# vme_can_can.net
KiCad netlist of a schematic drawn in Altium Designer
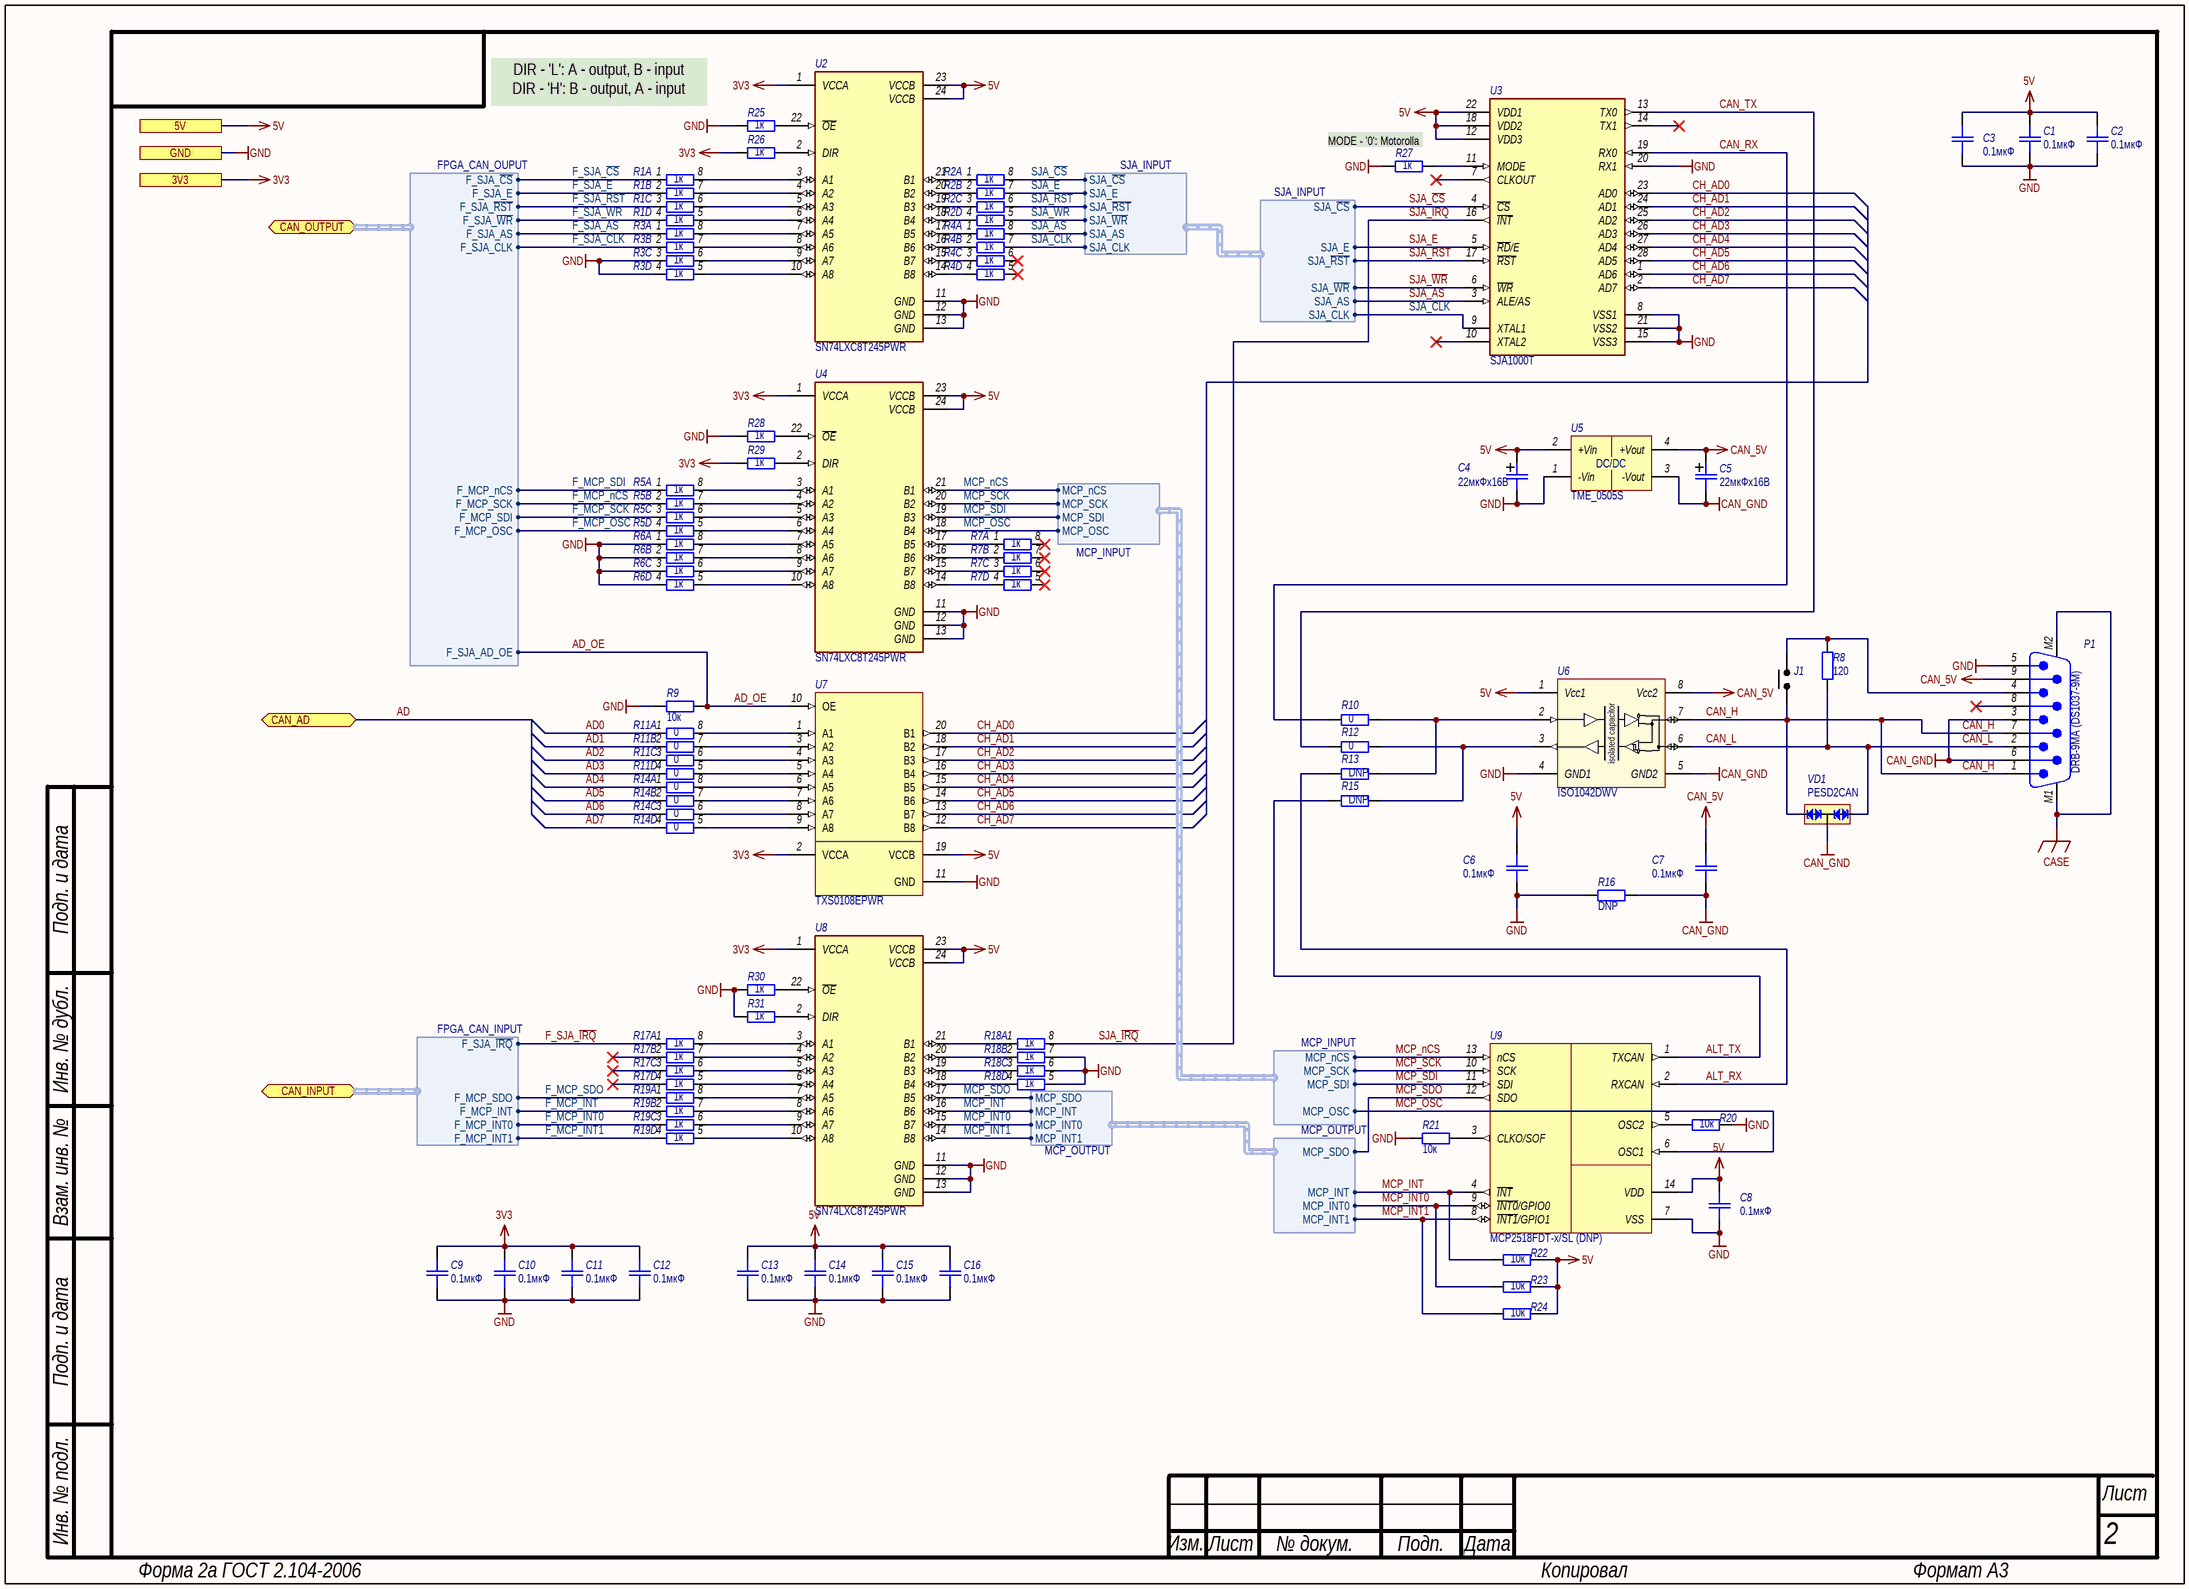
[diagram p0: vme_can_can.SchDoc]

(export (version "E")
  (design (tool "Eeschema 10.0.6"))
  (components
    (comp (ref "C1")
      (value "0.1мкФ")
      (footprint "SMD_C0805")
      (description "Capacitor")
      (libsource (lib "Passive") (part "Capacitor"))
    )
    (comp (ref "C2")
      (value "0.1мкФ")
      (footprint "SMD_C0805")
      (description "Capacitor")
      (libsource (lib "Passive") (part "Capacitor"))
    )
    (comp (ref "C3")
      (value "0.1мкФ")
      (footprint "SMD_C0805")
      (description "Capacitor")
      (libsource (lib "Passive") (part "Capacitor"))
    )
    (comp (ref "C4")
      (value "22мкФх16В")
      (footprint "SMD_size_B")
      (description "Polarized capacitor")
      (fields (field (name "Comment") "OS K53-68"))
      (libsource (lib "Passive") (part "Capacitor_pol"))
    )
    (comp (ref "C5")
      (value "22мкФх16В")
      (footprint "SMD_size_B")
      (description "Polarized capacitor")
      (fields (field (name "Comment") "OS K53-68"))
      (libsource (lib "Passive") (part "Capacitor_pol"))
    )
    (comp (ref "C6")
      (value "0.1мкФ")
      (footprint "SMD_C0805")
      (description "Capacitor")
      (libsource (lib "Passive") (part "Capacitor"))
    )
    (comp (ref "C7")
      (value "0.1мкФ")
      (footprint "SMD_C0805")
      (description "Capacitor")
      (libsource (lib "Passive") (part "Capacitor"))
    )
    (comp (ref "C8")
      (value "0.1мкФ")
      (footprint "SMD_C0805")
      (description "Capacitor")
      (libsource (lib "Passive") (part "Capacitor"))
    )
    (comp (ref "C9")
      (value "0.1мкФ")
      (footprint "SMD_C0805")
      (description "Capacitor")
      (libsource (lib "Passive") (part "Capacitor"))
    )
    (comp (ref "C10")
      (value "0.1мкФ")
      (footprint "SMD_C0805")
      (description "Capacitor")
      (libsource (lib "Passive") (part "Capacitor"))
    )
    (comp (ref "C11")
      (value "0.1мкФ")
      (footprint "SMD_C0805")
      (description "Capacitor")
      (libsource (lib "Passive") (part "Capacitor"))
    )
    (comp (ref "C12")
      (value "0.1мкФ")
      (footprint "SMD_C0805")
      (description "Capacitor")
      (libsource (lib "Passive") (part "Capacitor"))
    )
    (comp (ref "C13")
      (value "0.1мкФ")
      (footprint "SMD_C0805")
      (description "Capacitor")
      (libsource (lib "Passive") (part "Capacitor"))
    )
    (comp (ref "C14")
      (value "0.1мкФ")
      (footprint "SMD_C0805")
      (description "Capacitor")
      (libsource (lib "Passive") (part "Capacitor"))
    )
    (comp (ref "C15")
      (value "0.1мкФ")
      (footprint "SMD_C0805")
      (description "Capacitor")
      (libsource (lib "Passive") (part "Capacitor"))
    )
    (comp (ref "C16")
      (value "0.1мкФ")
      (footprint "SMD_C0805")
      (description "Capacitor")
      (libsource (lib "Passive") (part "Capacitor"))
    )
    (comp (ref "J1")
      (value "Jumper 2")
      (footprint "PLS-2")
      (description "Jumper, 2-Pin, Dual row")
      (libsource (lib "Connector") (part "Jumper 2"))
    )
    (comp (ref "P1")
      (value "DRB-9MA")
      (footprint "DRB-9MA")
      (description "D-SUB 9 pins, Male PCB Connector with Hex Screw WR-DSUB, 8.08 mm, Angled")
      (fields
        (field (name "MANUFACTURER") "Wurth Elektronik")
        (field (name "PART NUMBER") "618009231221")
        (field (name "НАИМЕНОВАНИЕ") "DRB-9MA (DS1037-9M)")
        (field (name "PUBLISHER") "WurthElektronik")
      )
      (libsource (lib "Connector") (part "DRB-9MA"))
    )
    (comp (ref "R1")
      (value "1к")
      (footprint "TC124")
      (description "4 Chip Resistor Array")
      (libsource (lib "Passive") (part "Resistor-4"))
    )
    (comp (ref "R2")
      (value "1к")
      (footprint "TC124")
      (description "4 Chip Resistor Array")
      (libsource (lib "Passive") (part "Resistor-4"))
    )
    (comp (ref "R3")
      (value "1к")
      (footprint "TC124")
      (description "4 Chip Resistor Array")
      (libsource (lib "Passive") (part "Resistor-4"))
    )
    (comp (ref "R4")
      (value "1к")
      (footprint "TC124")
      (description "4 Chip Resistor Array")
      (libsource (lib "Passive") (part "Resistor-4"))
    )
    (comp (ref "R5")
      (value "1к")
      (footprint "TC124")
      (description "4 Chip Resistor Array")
      (libsource (lib "Passive") (part "Resistor-4"))
    )
    (comp (ref "R6")
      (value "1к")
      (footprint "TC124")
      (description "4 Chip Resistor Array")
      (libsource (lib "Passive") (part "Resistor-4"))
    )
    (comp (ref "R7")
      (value "1к")
      (footprint "TC124")
      (description "4 Chip Resistor Array")
      (libsource (lib "Passive") (part "Resistor-4"))
    )
    (comp (ref "R8")
      (value "120")
      (footprint "SMD_0805")
      (description "Resistor")
      (libsource (lib "") (part "Resistor_2"))
    )
    (comp (ref "R9")
      (value "10к")
      (footprint "SMD_0805")
      (description "Resistor")
      (libsource (lib "Passive") (part "Resistor"))
    )
    (comp (ref "R10")
      (value "0")
      (footprint "SMD_0805")
      (description "Resistor")
      (libsource (lib "Passive") (part "Resistor"))
    )
    (comp (ref "R11")
      (value "0")
      (footprint "TC124")
      (description "4 Chip Resistor Array")
      (libsource (lib "Passive") (part "Resistor-4"))
    )
    (comp (ref "R12")
      (value "0")
      (footprint "SMD_0805")
      (description "Resistor")
      (libsource (lib "Passive") (part "Resistor"))
    )
    (comp (ref "R13")
      (value "DNP")
      (footprint "SMD_0805")
      (description "Resistor")
      (libsource (lib "Passive") (part "Resistor"))
    )
    (comp (ref "R14")
      (value "0")
      (footprint "TC124")
      (description "4 Chip Resistor Array")
      (libsource (lib "Passive") (part "Resistor-4"))
    )
    (comp (ref "R15")
      (value "DNP")
      (footprint "SMD_0805")
      (description "Resistor")
      (libsource (lib "Passive") (part "Resistor"))
    )
    (comp (ref "R16")
      (value "DNP")
      (footprint "SMD_0805")
      (description "Resistor")
      (libsource (lib "Passive") (part "Resistor"))
    )
    (comp (ref "R17")
      (value "1к")
      (footprint "TC124")
      (description "4 Chip Resistor Array")
      (libsource (lib "Passive") (part "Resistor-4"))
    )
    (comp (ref "R18")
      (value "1к")
      (footprint "TC124")
      (description "4 Chip Resistor Array")
      (libsource (lib "Passive") (part "Resistor-4"))
    )
    (comp (ref "R19")
      (value "1к")
      (footprint "TC124")
      (description "4 Chip Resistor Array")
      (libsource (lib "Passive") (part "Resistor-4"))
    )
    (comp (ref "R20")
      (value "10к")
      (footprint "SMD_0805")
      (description "Resistor")
      (libsource (lib "Passive") (part "Resistor"))
    )
    (comp (ref "R21")
      (value "10к")
      (footprint "SMD_0805")
      (description "Resistor")
      (libsource (lib "") (part "Resistor_1"))
    )
    (comp (ref "R22")
      (value "10к")
      (footprint "SMD_0805")
      (description "Resistor")
      (libsource (lib "Passive") (part "Resistor"))
    )
    (comp (ref "R23")
      (value "10к")
      (footprint "SMD_0805")
      (description "Resistor")
      (libsource (lib "Passive") (part "Resistor"))
    )
    (comp (ref "R24")
      (value "10к")
      (footprint "SMD_0805")
      (description "Resistor")
      (libsource (lib "Passive") (part "Resistor"))
    )
    (comp (ref "R25")
      (value "1к")
      (footprint "SMD_0805")
      (description "Resistor")
      (libsource (lib "Passive") (part "Resistor"))
    )
    (comp (ref "R26")
      (value "1к")
      (footprint "SMD_0805")
      (description "Resistor")
      (libsource (lib "Passive") (part "Resistor"))
    )
    (comp (ref "R27")
      (value "1к")
      (footprint "SMD_0805")
      (description "Resistor")
      (libsource (lib "Passive") (part "Resistor"))
    )
    (comp (ref "R28")
      (value "1к")
      (footprint "SMD_0805")
      (description "Resistor")
      (libsource (lib "Passive") (part "Resistor"))
    )
    (comp (ref "R29")
      (value "1к")
      (footprint "SMD_0805")
      (description "Resistor")
      (libsource (lib "Passive") (part "Resistor"))
    )
    (comp (ref "R30")
      (value "1к")
      (footprint "SMD_0805")
      (description "Resistor")
      (libsource (lib "Passive") (part "Resistor"))
    )
    (comp (ref "R31")
      (value "1к")
      (footprint "SMD_0805")
      (description "Resistor")
      (libsource (lib "Passive") (part "Resistor"))
    )
    (comp (ref "U2")
      (value "SN74LXC8T245PWR")
      (footprint "TSSOP-24")
      (description "Dual-Supply Bus Transceiver with Configurable Level Shifting\r\nand 3-State Outputs")
      (fields (field (name "НАИМЕНОВАНИЕ") "SN74LXC8T245PWR"))
      (libsource (lib "Transceiver") (part "SN74LXC8T245PWR"))
    )
    (comp (ref "U3")
      (value "SJA1000T")
      (footprint "SO28")
      (description "IC STAND-ALONE CAN CTRLR 28-SOIC")
      (fields
        (field (name "MANUFACTURER PART NUMBER") "SJA1000T/N1,118")
        (field (name "OCTOPART") "https://octopart.com/sja1000t%2Fn1%2C118-nxp+semiconductors-9518151")
        (field (name "НАИМЕНОВАНИЕ") "SJA1000T")
      )
      (libsource (lib "Interface_Controller") (part "SJA1000"))
    )
    (comp (ref "U4")
      (value "SN74LXC8T245PWR")
      (footprint "TSSOP-24")
      (description "Dual-Supply Bus Transceiver with Configurable Level Shifting\r\nand 3-State Outputs")
      (fields (field (name "НАИМЕНОВАНИЕ") "SN74LXC8T245PWR"))
      (libsource (lib "Transceiver") (part "SN74LXC8T245PWR"))
    )
    (comp (ref "U5")
      (value "TME_0505S")
      (footprint "PCBComponent_1")
      (description "DC-DC, 1W, Fixed input voltage, isolated & unregulated single output")
      (fields (field (name "НАИМЕНОВАНИЕ") "TME_0505S"))
      (libsource (lib "DC_DC") (part "TME_xxxxS"))
    )
    (comp (ref "U6")
      (value "ISO1042")
      (footprint "SOIC-8-WIDE")
      (description "Isolated CAN Transceiver")
      (fields (field (name "НАИМЕНОВАНИЕ") "ISO1042DWV"))
      (libsource (lib "Transceiver") (part "ISO1042"))
    )
    (comp (ref "U7")
      (value "TXS0108EPWR")
      (footprint "TSSOP-20")
      (fields (field (name "НАИМЕНОВАНИЕ") "TXS0108EPWR"))
      (libsource (lib "Transceiver") (part "TXS0108EPWR"))
    )
    (comp (ref "U8")
      (value "SN74LXC8T245PWR")
      (footprint "TSSOP-24")
      (description "Dual-Supply Bus Transceiver with Configurable Level Shifting\r\nand 3-State Outputs")
      (fields (field (name "НАИМЕНОВАНИЕ") "SN74LXC8T245PWR"))
      (libsource (lib "Transceiver") (part "SN74LXC8T245PWR"))
    )
    (comp (ref "U9")
      (value "MCP2518FDT-x/SL")
      (footprint "SOIC-14")
      (description "CAN FD Controller with SPI Interface")
      (fields (field (name "НАИМЕНОВАНИЕ") "MCP2518FDT-x/SL (DNP)"))
      (libsource (lib "Interface_Controller") (part "MCP2518FDT-x_SL"))
    )
    (comp (ref "VD1")
      (value "PESD2CAN")
      (footprint "SOT-23")
      (description "CAN bus ESD protection diode")
      (fields (field (name "НАИМЕНОВАНИЕ") "PESD2CAN"))
      (libsource (lib "Diod") (part "PESD2CAN"))
    )
  )
  (nets
    (net (code "7") (name "/AD0") (class "Default")
      (node (ref "R11") (pin "1") (pinfunction "1_1") (pintype "passive"))
    )
    (net (code "8") (name "/AD1") (class "Default")
      (node (ref "R11") (pin "2") (pinfunction "2_2") (pintype "passive"))
    )
    (net (code "9") (name "/AD2") (class "Default")
      (node (ref "R11") (pin "3") (pinfunction "3_3") (pintype "passive"))
    )
    (net (code "10") (name "/AD3") (class "Default")
      (node (ref "R11") (pin "4") (pinfunction "4_4") (pintype "passive"))
    )
    (net (code "11") (name "/AD4") (class "Default")
      (node (ref "R14") (pin "1") (pinfunction "1_1") (pintype "passive"))
    )
    (net (code "12") (name "/AD5") (class "Default")
      (node (ref "R14") (pin "2") (pinfunction "2_2") (pintype "passive"))
    )
    (net (code "13") (name "/AD6") (class "Default")
      (node (ref "R14") (pin "3") (pinfunction "3_3") (pintype "passive"))
    )
    (net (code "14") (name "/AD7") (class "Default")
      (node (ref "R14") (pin "4") (pinfunction "4_4") (pintype "passive"))
    )
    (net (code "15") (name "/AD_OE") (class "Default")
      (node (ref "R9") (pin "1") (pinfunction "1_1") (pintype "passive"))
      (node (ref "U7") (pin "10") (pinfunction "OE_10") (pintype "input"))
    )
    (net (code "16") (name "/ALT_RX") (class "Default")
      (node (ref "R13") (pin "2") (pinfunction "2_2") (pintype "passive"))
      (node (ref "U9") (pin "2") (pinfunction "RXCAN_2") (pintype "input"))
    )
    (net (code "17") (name "/ALT_TX") (class "Default")
      (node (ref "R15") (pin "2") (pinfunction "2_2") (pintype "passive"))
      (node (ref "U9") (pin "1") (pinfunction "TXCAN_1") (pintype "output"))
    )
    (net (code "18") (name "/CAN_H") (class "Default")
      (node (ref "J1") (pin "1") (pinfunction "1_1") (pintype "passive"))
      (node (ref "P1") (pin "1") (pinfunction "1_1") (pintype "passive"))
      (node (ref "P1") (pin "7") (pinfunction "7_7") (pintype "passive"))
      (node (ref "U6") (pin "7") (pinfunction "CANH_7") (pintype "bidirectional"))
      (node (ref "VD1") (pin "2") (pinfunction "C2_2") (pintype "passive"))
    )
    (net (code "19") (name "/CAN_L") (class "Default")
      (node (ref "P1") (pin "2") (pinfunction "2_2") (pintype "passive"))
      (node (ref "R8") (pin "1") (pinfunction "1_1") (pintype "passive"))
      (node (ref "U6") (pin "6") (pinfunction "CANL_6") (pintype "bidirectional"))
      (node (ref "VD1") (pin "1") (pinfunction "C1_1") (pintype "passive"))
    )
    (net (code "20") (name "/CAN_RX") (class "Default")
      (node (ref "R10") (pin "2") (pinfunction "2_2") (pintype "passive"))
      (node (ref "U3") (pin "19") (pinfunction "RX0_19") (pintype "input"))
    )
    (net (code "21") (name "/CAN_TX") (class "Default")
      (node (ref "R12") (pin "2") (pinfunction "2_2") (pintype "passive"))
      (node (ref "U3") (pin "13") (pinfunction "TX0_13") (pintype "output"))
    )
    (net (code "22") (name "/CH_AD0") (class "Default")
      (node (ref "U3") (pin "23") (pinfunction "AD0_23") (pintype "bidirectional"))
      (node (ref "U7") (pin "20") (pinfunction "B1_20") (pintype "output"))
    )
    (net (code "23") (name "/CH_AD1") (class "Default")
      (node (ref "U3") (pin "24") (pinfunction "AD1_24") (pintype "bidirectional"))
      (node (ref "U7") (pin "18") (pinfunction "B2_18") (pintype "output"))
    )
    (net (code "24") (name "/CH_AD2") (class "Default")
      (node (ref "U3") (pin "25") (pinfunction "AD2_25") (pintype "bidirectional"))
      (node (ref "U7") (pin "17") (pinfunction "B3_17") (pintype "output"))
    )
    (net (code "25") (name "/CH_AD3") (class "Default")
      (node (ref "U3") (pin "26") (pinfunction "AD3_26") (pintype "bidirectional"))
      (node (ref "U7") (pin "16") (pinfunction "B4_16") (pintype "output"))
    )
    (net (code "26") (name "/CH_AD4") (class "Default")
      (node (ref "U3") (pin "27") (pinfunction "AD4_27") (pintype "bidirectional"))
      (node (ref "U7") (pin "15") (pinfunction "B5_15") (pintype "output"))
    )
    (net (code "27") (name "/CH_AD5") (class "Default")
      (node (ref "U3") (pin "28") (pinfunction "AD5_28") (pintype "bidirectional"))
      (node (ref "U7") (pin "14") (pinfunction "B6_14") (pintype "output"))
    )
    (net (code "28") (name "/CH_AD6") (class "Default")
      (node (ref "U3") (pin "1") (pinfunction "AD6_1") (pintype "bidirectional"))
      (node (ref "U7") (pin "13") (pinfunction "B7_13") (pintype "output"))
    )
    (net (code "29") (name "/CH_AD7") (class "Default")
      (node (ref "U3") (pin "2") (pinfunction "AD7_2") (pintype "bidirectional"))
      (node (ref "U7") (pin "12") (pinfunction "B8_12") (pintype "output"))
    )
    (net (code "30") (name "/F_MCP_INT") (class "Default")
      (node (ref "R19") (pin "2") (pinfunction "2_2") (pintype "passive"))
    )
    (net (code "31") (name "/F_MCP_INT0") (class "Default")
      (node (ref "R19") (pin "3") (pinfunction "3_3") (pintype "passive"))
    )
    (net (code "32") (name "/F_MCP_INT1") (class "Default")
      (node (ref "R19") (pin "4") (pinfunction "4_4") (pintype "passive"))
    )
    (net (code "33") (name "/F_MCP_OSC") (class "Default")
      (node (ref "R5") (pin "4") (pinfunction "4_4") (pintype "passive"))
    )
    (net (code "34") (name "/F_MCP_SCK") (class "Default")
      (node (ref "R5") (pin "3") (pinfunction "3_3") (pintype "passive"))
    )
    (net (code "35") (name "/F_MCP_SDI") (class "Default")
      (node (ref "R5") (pin "1") (pinfunction "1_1") (pintype "passive"))
    )
    (net (code "36") (name "/F_MCP_SDO") (class "Default")
      (node (ref "R19") (pin "1") (pinfunction "1_1") (pintype "passive"))
    )
    (net (code "37") (name "/F_MCP_nCS") (class "Default")
      (node (ref "R5") (pin "2") (pinfunction "2_2") (pintype "passive"))
    )
    (net (code "38") (name "/F_SJA_AS") (class "Default")
      (node (ref "R3") (pin "1") (pinfunction "1_1") (pintype "passive"))
    )
    (net (code "39") (name "/F_SJA_CLK") (class "Default")
      (node (ref "R3") (pin "2") (pinfunction "2_2") (pintype "passive"))
    )
    (net (code "40") (name "/F_SJA_E") (class "Default")
      (node (ref "R1") (pin "2") (pinfunction "2_2") (pintype "passive"))
    )
    (net (code "41") (name "/F_SJA_~{CS}") (class "Default")
      (node (ref "R1") (pin "1") (pinfunction "1_1") (pintype "passive"))
    )
    (net (code "42") (name "/F_SJA_~{IRQ}") (class "Default")
      (node (ref "R17") (pin "1") (pinfunction "1_1") (pintype "passive"))
    )
    (net (code "43") (name "/F_SJA_~{RST}") (class "Default")
      (node (ref "R1") (pin "3") (pinfunction "3_3") (pintype "passive"))
    )
    (net (code "44") (name "/F_SJA_~{WR}") (class "Default")
      (node (ref "R1") (pin "4") (pinfunction "4_4") (pintype "passive"))
    )
    (net (code "45") (name "/MCP_INT") (class "Default")
      (node (ref "R22") (pin "2") (pinfunction "2_2") (pintype "passive"))
      (node (ref "U8") (pin "16") (pinfunction "B6_16") (pintype "bidirectional"))
      (node (ref "U9") (pin "4") (pinfunction "~{INT}_4") (pintype "output"))
    )
    (net (code "46") (name "/MCP_INT0") (class "Default")
      (node (ref "R23") (pin "2") (pinfunction "2_2") (pintype "passive"))
      (node (ref "U8") (pin "15") (pinfunction "B7_15") (pintype "bidirectional"))
      (node (ref "U9") (pin "9") (pinfunction "~{INT0}/GPIO0_9") (pintype "bidirectional"))
    )
    (net (code "47") (name "/MCP_INT1") (class "Default")
      (node (ref "R24") (pin "2") (pinfunction "2_2") (pintype "passive"))
      (node (ref "U8") (pin "14") (pinfunction "B8_14") (pintype "bidirectional"))
      (node (ref "U9") (pin "8") (pinfunction "~{INT1}/GPIO1_8") (pintype "bidirectional"))
    )
    (net (code "48") (name "/MCP_OSC") (class "Default")
      (node (ref "U4") (pin "18") (pinfunction "B4_18") (pintype "bidirectional"))
      (node (ref "U9") (pin "6") (pinfunction "OSC1_6") (pintype "input"))
    )
    (net (code "49") (name "/MCP_SCK") (class "Default")
      (node (ref "U4") (pin "20") (pinfunction "B2_20") (pintype "bidirectional"))
      (node (ref "U9") (pin "10") (pinfunction "SCK_10") (pintype "input"))
    )
    (net (code "50") (name "/MCP_SDI") (class "Default")
      (node (ref "U4") (pin "19") (pinfunction "B3_19") (pintype "bidirectional"))
      (node (ref "U9") (pin "11") (pinfunction "SDI_11") (pintype "input"))
    )
    (net (code "51") (name "/MCP_SDO") (class "Default")
      (node (ref "U8") (pin "17") (pinfunction "B5_17") (pintype "bidirectional"))
      (node (ref "U9") (pin "12") (pinfunction "SDO_12") (pintype "output"))
    )
    (net (code "52") (name "/MCP_nCS") (class "Default")
      (node (ref "U4") (pin "21") (pinfunction "B1_21") (pintype "bidirectional"))
      (node (ref "U9") (pin "13") (pinfunction "nCS_13") (pintype "input"))
    )
    (net (code "53") (name "/SJA_AS") (class "Default")
      (node (ref "R4") (pin "8") (pinfunction "8_8") (pintype "passive"))
      (node (ref "U3") (pin "3") (pinfunction "ALE/AS_3") (pintype "input"))
    )
    (net (code "54") (name "/SJA_CLK") (class "Default")
      (node (ref "R4") (pin "7") (pinfunction "7_7") (pintype "passive"))
      (node (ref "U3") (pin "9") (pinfunction "XTAL1_9") (pintype "passive"))
    )
    (net (code "55") (name "/SJA_E") (class "Default")
      (node (ref "R2") (pin "7") (pinfunction "7_7") (pintype "passive"))
      (node (ref "U3") (pin "5") (pinfunction "~{RD}/E_5") (pintype "input"))
    )
    (net (code "56") (name "/SJA_~{CS}") (class "Default")
      (node (ref "R2") (pin "8") (pinfunction "8_8") (pintype "passive"))
      (node (ref "U3") (pin "4") (pinfunction "~{CS}_4") (pintype "input"))
    )
    (net (code "57") (name "/SJA_~{IRQ}") (class "Default")
      (node (ref "R18") (pin "8") (pinfunction "8_8") (pintype "passive"))
      (node (ref "U3") (pin "16") (pinfunction "~{INT}_16") (pintype "output"))
    )
    (net (code "58") (name "/SJA_~{RST}") (class "Default")
      (node (ref "R2") (pin "6") (pinfunction "6_6") (pintype "passive"))
      (node (ref "U3") (pin "17") (pinfunction "~{RST}_17") (pintype "input"))
    )
    (net (code "59") (name "/SJA_~{WR}") (class "Default")
      (node (ref "R2") (pin "5") (pinfunction "5_5") (pintype "passive"))
      (node (ref "U3") (pin "6") (pinfunction "~{WR}_6") (pintype "input"))
    )
    (net (code "66") (name "3V3") (class "Default")
      (node (ref "C10") (pin "2") (pinfunction "2_2") (pintype "passive"))
      (node (ref "C11") (pin "2") (pinfunction "2_2") (pintype "passive"))
      (node (ref "C12") (pin "2") (pinfunction "2_2") (pintype "passive"))
      (node (ref "C9") (pin "2") (pinfunction "2_2") (pintype "passive"))
      (node (ref "R26") (pin "2") (pinfunction "2_2") (pintype "passive"))
      (node (ref "R29") (pin "2") (pinfunction "2_2") (pintype "passive"))
      (node (ref "U2") (pin "1") (pinfunction "VCCA_1") (pintype "power_in"))
      (node (ref "U4") (pin "1") (pinfunction "VCCA_1") (pintype "power_in"))
      (node (ref "U7") (pin "2") (pinfunction "VCCA_2") (pintype "power_in"))
      (node (ref "U8") (pin "1") (pinfunction "VCCA_1") (pintype "power_in"))
    )
    (net (code "67") (name "5V") (class "Default")
      (node (ref "C1") (pin "2") (pinfunction "2_2") (pintype "passive"))
      (node (ref "C13") (pin "2") (pinfunction "2_2") (pintype "passive"))
      (node (ref "C14") (pin "2") (pinfunction "2_2") (pintype "passive"))
      (node (ref "C15") (pin "2") (pinfunction "2_2") (pintype "passive"))
      (node (ref "C16") (pin "2") (pinfunction "2_2") (pintype "passive"))
      (node (ref "C2") (pin "2") (pinfunction "2_2") (pintype "passive"))
      (node (ref "C3") (pin "2") (pinfunction "2_2") (pintype "passive"))
      (node (ref "C4") (pin "1") (pinfunction "1_1") (pintype "passive"))
      (node (ref "C6") (pin "2") (pinfunction "2_2") (pintype "passive"))
      (node (ref "C8") (pin "2") (pinfunction "2_2") (pintype "passive"))
      (node (ref "R22") (pin "1") (pinfunction "1_1") (pintype "passive"))
      (node (ref "R23") (pin "1") (pinfunction "1_1") (pintype "passive"))
      (node (ref "R24") (pin "1") (pinfunction "1_1") (pintype "passive"))
      (node (ref "U2") (pin "23") (pinfunction "VCCB_23") (pintype "power_in"))
      (node (ref "U2") (pin "24") (pinfunction "VCCB_24") (pintype "power_in"))
      (node (ref "U3") (pin "12") (pinfunction "VDD3_12") (pintype "power_in"))
      (node (ref "U3") (pin "18") (pinfunction "VDD2_18") (pintype "power_in"))
      (node (ref "U3") (pin "22") (pinfunction "VDD1_22") (pintype "power_in"))
      (node (ref "U4") (pin "23") (pinfunction "VCCB_23") (pintype "power_in"))
      (node (ref "U4") (pin "24") (pinfunction "VCCB_24") (pintype "power_in"))
      (node (ref "U5") (pin "2") (pinfunction "+Vin_2") (pintype "power_in"))
      (node (ref "U6") (pin "1") (pinfunction "Vcc1_1") (pintype "power_in"))
      (node (ref "U7") (pin "19") (pinfunction "VCCB_19") (pintype "power_in"))
      (node (ref "U8") (pin "23") (pinfunction "VCCB_23") (pintype "power_in"))
      (node (ref "U8") (pin "24") (pinfunction "VCCB_24") (pintype "power_in"))
      (node (ref "U9") (pin "14") (pinfunction "VDD_14") (pintype "power_in"))
    )
    (net (code "68") (name "CAN_5V") (class "Default")
      (node (ref "C5") (pin "1") (pinfunction "1_1") (pintype "passive"))
      (node (ref "C7") (pin "2") (pinfunction "2_2") (pintype "passive"))
      (node (ref "P1") (pin "9") (pinfunction "9_9") (pintype "passive"))
      (node (ref "U5") (pin "4") (pinfunction "+Vout_4") (pintype "power_in"))
      (node (ref "U6") (pin "8") (pinfunction "Vcc2_8") (pintype "power_in"))
    )
    (net (code "69") (name "CAN_GND") (class "Default")
      (node (ref "C5") (pin "2") (pinfunction "2_2") (pintype "passive"))
      (node (ref "C7") (pin "1") (pinfunction "1_1") (pintype "passive"))
      (node (ref "P1") (pin "3") (pinfunction "3_3") (pintype "passive"))
      (node (ref "P1") (pin "6") (pinfunction "6_6") (pintype "passive"))
      (node (ref "R16") (pin "1") (pinfunction "1_1") (pintype "passive"))
      (node (ref "U5") (pin "3") (pinfunction "-Vout_3") (pintype "power_in"))
      (node (ref "U6") (pin "5") (pinfunction "GND2_5") (pintype "power_in"))
      (node (ref "VD1") (pin "3") (pinfunction "CC_3") (pintype "passive"))
    )
    (net (code "70") (name "CASE") (class "Default")
      (node (ref "P1") (pin "M1") (pinfunction "M1_M1") (pintype "passive"))
      (node (ref "P1") (pin "M2") (pinfunction "M2_M2") (pintype "passive"))
    )
    (net (code "71") (name "GND") (class "Default")
      (node (ref "C1") (pin "1") (pinfunction "1_1") (pintype "passive"))
      (node (ref "C10") (pin "1") (pinfunction "1_1") (pintype "passive"))
      (node (ref "C11") (pin "1") (pinfunction "1_1") (pintype "passive"))
      (node (ref "C12") (pin "1") (pinfunction "1_1") (pintype "passive"))
      (node (ref "C13") (pin "1") (pinfunction "1_1") (pintype "passive"))
      (node (ref "C14") (pin "1") (pinfunction "1_1") (pintype "passive"))
      (node (ref "C15") (pin "1") (pinfunction "1_1") (pintype "passive"))
      (node (ref "C16") (pin "1") (pinfunction "1_1") (pintype "passive"))
      (node (ref "C2") (pin "1") (pinfunction "1_1") (pintype "passive"))
      (node (ref "C3") (pin "1") (pinfunction "1_1") (pintype "passive"))
      (node (ref "C4") (pin "2") (pinfunction "2_2") (pintype "passive"))
      (node (ref "C6") (pin "1") (pinfunction "1_1") (pintype "passive"))
      (node (ref "C8") (pin "1") (pinfunction "1_1") (pintype "passive"))
      (node (ref "C9") (pin "1") (pinfunction "1_1") (pintype "passive"))
      (node (ref "P1") (pin "5") (pinfunction "5_5") (pintype "passive"))
      (node (ref "R16") (pin "2") (pinfunction "2_2") (pintype "passive"))
      (node (ref "R18") (pin "5") (pinfunction "5_5") (pintype "passive"))
      (node (ref "R18") (pin "6") (pinfunction "6_6") (pintype "passive"))
      (node (ref "R18") (pin "7") (pinfunction "7_7") (pintype "passive"))
      (node (ref "R20") (pin "1") (pinfunction "1_1") (pintype "passive"))
      (node (ref "R21") (pin "1") (pinfunction "1_1") (pintype "passive"))
      (node (ref "R25") (pin "2") (pinfunction "2_2") (pintype "passive"))
      (node (ref "R27") (pin "2") (pinfunction "2_2") (pintype "passive"))
      (node (ref "R28") (pin "2") (pinfunction "2_2") (pintype "passive"))
      (node (ref "R3") (pin "3") (pinfunction "3_3") (pintype "passive"))
      (node (ref "R3") (pin "4") (pinfunction "4_4") (pintype "passive"))
      (node (ref "R30") (pin "2") (pinfunction "2_2") (pintype "passive"))
      (node (ref "R31") (pin "2") (pinfunction "2_2") (pintype "passive"))
      (node (ref "R6") (pin "1") (pinfunction "1_1") (pintype "passive"))
      (node (ref "R6") (pin "2") (pinfunction "2_2") (pintype "passive"))
      (node (ref "R6") (pin "3") (pinfunction "3_3") (pintype "passive"))
      (node (ref "R6") (pin "4") (pinfunction "4_4") (pintype "passive"))
      (node (ref "R9") (pin "2") (pinfunction "2_2") (pintype "passive"))
      (node (ref "U2") (pin "11") (pinfunction "GND_11") (pintype "power_in"))
      (node (ref "U2") (pin "12") (pinfunction "GND_12") (pintype "power_in"))
      (node (ref "U2") (pin "13") (pinfunction "GND_13") (pintype "power_in"))
      (node (ref "U3") (pin "15") (pinfunction "VSS3_15") (pintype "power_in"))
      (node (ref "U3") (pin "20") (pinfunction "RX1_20") (pintype "input"))
      (node (ref "U3") (pin "21") (pinfunction "VSS2_21") (pintype "power_in"))
      (node (ref "U3") (pin "8") (pinfunction "VSS1_8") (pintype "power_in"))
      (node (ref "U4") (pin "11") (pinfunction "GND_11") (pintype "power_in"))
      (node (ref "U4") (pin "12") (pinfunction "GND_12") (pintype "power_in"))
      (node (ref "U4") (pin "13") (pinfunction "GND_13") (pintype "power_in"))
      (node (ref "U5") (pin "1") (pinfunction "-Vin_1") (pintype "power_in"))
      (node (ref "U6") (pin "4") (pinfunction "GND1_4") (pintype "power_in"))
      (node (ref "U7") (pin "11") (pinfunction "GND_11") (pintype "power_in"))
      (node (ref "U8") (pin "11") (pinfunction "GND_11") (pintype "power_in"))
      (node (ref "U8") (pin "12") (pinfunction "GND_12") (pintype "power_in"))
      (node (ref "U8") (pin "13") (pinfunction "GND_13") (pintype "power_in"))
      (node (ref "U9") (pin "7") (pinfunction "VSS_7") (pintype "power_in"))
    )
    (net (code "72") (name "Net-(J1-Pad2)") (class "Default")
      (node (ref "J1") (pin "2") (pinfunction "2_2") (pintype "passive"))
      (node (ref "P1") (pin "4") (pinfunction "4_4") (pintype "passive"))
      (node (ref "R8") (pin "2") (pinfunction "2_2") (pintype "passive"))
    )
    (net (code "73") (name "Net-(U2-A1)") (class "Default")
      (node (ref "R1") (pin "8") (pinfunction "8_8") (pintype "passive"))
      (node (ref "U2") (pin "3") (pinfunction "A1_3") (pintype "bidirectional"))
    )
    (net (code "74") (name "Net-(U2-A2)") (class "Default")
      (node (ref "R1") (pin "7") (pinfunction "7_7") (pintype "passive"))
      (node (ref "U2") (pin "4") (pinfunction "A2_4") (pintype "bidirectional"))
    )
    (net (code "75") (name "Net-(U2-A3)") (class "Default")
      (node (ref "R1") (pin "6") (pinfunction "6_6") (pintype "passive"))
      (node (ref "U2") (pin "5") (pinfunction "A3_5") (pintype "bidirectional"))
    )
    (net (code "76") (name "Net-(U2-A4)") (class "Default")
      (node (ref "R1") (pin "5") (pinfunction "5_5") (pintype "passive"))
      (node (ref "U2") (pin "6") (pinfunction "A4_6") (pintype "bidirectional"))
    )
    (net (code "77") (name "Net-(U2-A5)") (class "Default")
      (node (ref "R3") (pin "8") (pinfunction "8_8") (pintype "passive"))
      (node (ref "U2") (pin "7") (pinfunction "A5_7") (pintype "bidirectional"))
    )
    (net (code "78") (name "Net-(U2-A6)") (class "Default")
      (node (ref "R3") (pin "7") (pinfunction "7_7") (pintype "passive"))
      (node (ref "U2") (pin "8") (pinfunction "A6_8") (pintype "bidirectional"))
    )
    (net (code "79") (name "Net-(U2-A7)") (class "Default")
      (node (ref "R3") (pin "6") (pinfunction "6_6") (pintype "passive"))
      (node (ref "U2") (pin "9") (pinfunction "A7_9") (pintype "bidirectional"))
    )
    (net (code "80") (name "Net-(U2-A8)") (class "Default")
      (node (ref "R3") (pin "5") (pinfunction "5_5") (pintype "passive"))
      (node (ref "U2") (pin "10") (pinfunction "A8_10") (pintype "bidirectional"))
    )
    (net (code "81") (name "Net-(U2-B1)") (class "Default")
      (node (ref "R2") (pin "1") (pinfunction "1_1") (pintype "passive"))
      (node (ref "U2") (pin "21") (pinfunction "B1_21") (pintype "bidirectional"))
    )
    (net (code "82") (name "Net-(U2-B2)") (class "Default")
      (node (ref "R2") (pin "2") (pinfunction "2_2") (pintype "passive"))
      (node (ref "U2") (pin "20") (pinfunction "B2_20") (pintype "bidirectional"))
    )
    (net (code "83") (name "Net-(U2-B3)") (class "Default")
      (node (ref "R2") (pin "3") (pinfunction "3_3") (pintype "passive"))
      (node (ref "U2") (pin "19") (pinfunction "B3_19") (pintype "bidirectional"))
    )
    (net (code "84") (name "Net-(U2-B4)") (class "Default")
      (node (ref "R2") (pin "4") (pinfunction "4_4") (pintype "passive"))
      (node (ref "U2") (pin "18") (pinfunction "B4_18") (pintype "bidirectional"))
    )
    (net (code "85") (name "Net-(U2-B5)") (class "Default")
      (node (ref "R4") (pin "1") (pinfunction "1_1") (pintype "passive"))
      (node (ref "U2") (pin "17") (pinfunction "B5_17") (pintype "bidirectional"))
    )
    (net (code "86") (name "Net-(U2-B6)") (class "Default")
      (node (ref "R4") (pin "2") (pinfunction "2_2") (pintype "passive"))
      (node (ref "U2") (pin "16") (pinfunction "B6_16") (pintype "bidirectional"))
    )
    (net (code "87") (name "Net-(U2-B7)") (class "Default")
      (node (ref "R4") (pin "3") (pinfunction "3_3") (pintype "passive"))
      (node (ref "U2") (pin "15") (pinfunction "B7_15") (pintype "bidirectional"))
    )
    (net (code "88") (name "Net-(U2-B8)") (class "Default")
      (node (ref "R4") (pin "4") (pinfunction "4_4") (pintype "passive"))
      (node (ref "U2") (pin "14") (pinfunction "B8_14") (pintype "bidirectional"))
    )
    (net (code "89") (name "Net-(U2-DIR)") (class "Default")
      (node (ref "R26") (pin "1") (pinfunction "1_1") (pintype "passive"))
      (node (ref "U2") (pin "2") (pinfunction "DIR_2") (pintype "input"))
    )
    (net (code "90") (name "Net-(U2-~{OE})") (class "Default")
      (node (ref "R25") (pin "1") (pinfunction "1_1") (pintype "passive"))
      (node (ref "U2") (pin "22") (pinfunction "~{OE}_22") (pintype "input"))
    )
    (net (code "91") (name "Net-(U3-MODE)") (class "Default")
      (node (ref "R27") (pin "1") (pinfunction "1_1") (pintype "passive"))
      (node (ref "U3") (pin "11") (pinfunction "MODE_11") (pintype "input"))
    )
    (net (code "92") (name "Net-(U4-A1)") (class "Default")
      (node (ref "R5") (pin "8") (pinfunction "8_8") (pintype "passive"))
      (node (ref "U4") (pin "3") (pinfunction "A1_3") (pintype "bidirectional"))
    )
    (net (code "93") (name "Net-(U4-A2)") (class "Default")
      (node (ref "R5") (pin "7") (pinfunction "7_7") (pintype "passive"))
      (node (ref "U4") (pin "4") (pinfunction "A2_4") (pintype "bidirectional"))
    )
    (net (code "94") (name "Net-(U4-A3)") (class "Default")
      (node (ref "R5") (pin "6") (pinfunction "6_6") (pintype "passive"))
      (node (ref "U4") (pin "5") (pinfunction "A3_5") (pintype "bidirectional"))
    )
    (net (code "95") (name "Net-(U4-A4)") (class "Default")
      (node (ref "R5") (pin "5") (pinfunction "5_5") (pintype "passive"))
      (node (ref "U4") (pin "6") (pinfunction "A4_6") (pintype "bidirectional"))
    )
    (net (code "96") (name "Net-(U4-A5)") (class "Default")
      (node (ref "R6") (pin "8") (pinfunction "8_8") (pintype "passive"))
      (node (ref "U4") (pin "7") (pinfunction "A5_7") (pintype "bidirectional"))
    )
    (net (code "97") (name "Net-(U4-A6)") (class "Default")
      (node (ref "R6") (pin "7") (pinfunction "7_7") (pintype "passive"))
      (node (ref "U4") (pin "8") (pinfunction "A6_8") (pintype "bidirectional"))
    )
    (net (code "98") (name "Net-(U4-A7)") (class "Default")
      (node (ref "R6") (pin "6") (pinfunction "6_6") (pintype "passive"))
      (node (ref "U4") (pin "9") (pinfunction "A7_9") (pintype "bidirectional"))
    )
    (net (code "99") (name "Net-(U4-A8)") (class "Default")
      (node (ref "R6") (pin "5") (pinfunction "5_5") (pintype "passive"))
      (node (ref "U4") (pin "10") (pinfunction "A8_10") (pintype "bidirectional"))
    )
    (net (code "100") (name "Net-(U4-B5)") (class "Default")
      (node (ref "R7") (pin "1") (pinfunction "1_1") (pintype "passive"))
      (node (ref "U4") (pin "17") (pinfunction "B5_17") (pintype "bidirectional"))
    )
    (net (code "101") (name "Net-(U4-B6)") (class "Default")
      (node (ref "R7") (pin "2") (pinfunction "2_2") (pintype "passive"))
      (node (ref "U4") (pin "16") (pinfunction "B6_16") (pintype "bidirectional"))
    )
    (net (code "102") (name "Net-(U4-B7)") (class "Default")
      (node (ref "R7") (pin "3") (pinfunction "3_3") (pintype "passive"))
      (node (ref "U4") (pin "15") (pinfunction "B7_15") (pintype "bidirectional"))
    )
    (net (code "103") (name "Net-(U4-B8)") (class "Default")
      (node (ref "R7") (pin "4") (pinfunction "4_4") (pintype "passive"))
      (node (ref "U4") (pin "14") (pinfunction "B8_14") (pintype "bidirectional"))
    )
    (net (code "104") (name "Net-(U4-DIR)") (class "Default")
      (node (ref "R29") (pin "1") (pinfunction "1_1") (pintype "passive"))
      (node (ref "U4") (pin "2") (pinfunction "DIR_2") (pintype "input"))
    )
    (net (code "105") (name "Net-(U4-~{OE})") (class "Default")
      (node (ref "R28") (pin "1") (pinfunction "1_1") (pintype "passive"))
      (node (ref "U4") (pin "22") (pinfunction "~{OE}_22") (pintype "input"))
    )
    (net (code "106") (name "Net-(U6-RXD)") (class "Default")
      (node (ref "R12") (pin "1") (pinfunction "1_1") (pintype "passive"))
      (node (ref "R15") (pin "1") (pinfunction "1_1") (pintype "passive"))
      (node (ref "U6") (pin "3") (pinfunction "RXD_3") (pintype "output"))
    )
    (net (code "107") (name "Net-(U6-TXD)") (class "Default")
      (node (ref "R10") (pin "1") (pinfunction "1_1") (pintype "passive"))
      (node (ref "R13") (pin "1") (pinfunction "1_1") (pintype "passive"))
      (node (ref "U6") (pin "2") (pinfunction "TXD_2") (pintype "input"))
    )
    (net (code "108") (name "Net-(U7-A1)") (class "Default")
      (node (ref "R11") (pin "8") (pinfunction "8_8") (pintype "passive"))
      (node (ref "U7") (pin "1") (pinfunction "A1_1") (pintype "input"))
    )
    (net (code "109") (name "Net-(U7-A2)") (class "Default")
      (node (ref "R11") (pin "7") (pinfunction "7_7") (pintype "passive"))
      (node (ref "U7") (pin "3") (pinfunction "A2_3") (pintype "input"))
    )
    (net (code "110") (name "Net-(U7-A3)") (class "Default")
      (node (ref "R11") (pin "6") (pinfunction "6_6") (pintype "passive"))
      (node (ref "U7") (pin "4") (pinfunction "A3_4") (pintype "input"))
    )
    (net (code "111") (name "Net-(U7-A4)") (class "Default")
      (node (ref "R11") (pin "5") (pinfunction "5_5") (pintype "passive"))
      (node (ref "U7") (pin "5") (pinfunction "A4_5") (pintype "input"))
    )
    (net (code "112") (name "Net-(U7-A5)") (class "Default")
      (node (ref "R14") (pin "8") (pinfunction "8_8") (pintype "passive"))
      (node (ref "U7") (pin "6") (pinfunction "A5_6") (pintype "input"))
    )
    (net (code "113") (name "Net-(U7-A6)") (class "Default")
      (node (ref "R14") (pin "7") (pinfunction "7_7") (pintype "passive"))
      (node (ref "U7") (pin "7") (pinfunction "A6_7") (pintype "input"))
    )
    (net (code "114") (name "Net-(U7-A7)") (class "Default")
      (node (ref "R14") (pin "6") (pinfunction "6_6") (pintype "passive"))
      (node (ref "U7") (pin "8") (pinfunction "A7_8") (pintype "input"))
    )
    (net (code "115") (name "Net-(U7-A8)") (class "Default")
      (node (ref "R14") (pin "5") (pinfunction "5_5") (pintype "passive"))
      (node (ref "U7") (pin "9") (pinfunction "A8_9") (pintype "input"))
    )
    (net (code "116") (name "Net-(U8-A1)") (class "Default")
      (node (ref "R17") (pin "8") (pinfunction "8_8") (pintype "passive"))
      (node (ref "U8") (pin "3") (pinfunction "A1_3") (pintype "bidirectional"))
    )
    (net (code "117") (name "Net-(U8-A2)") (class "Default")
      (node (ref "R17") (pin "7") (pinfunction "7_7") (pintype "passive"))
      (node (ref "U8") (pin "4") (pinfunction "A2_4") (pintype "bidirectional"))
    )
    (net (code "118") (name "Net-(U8-A3)") (class "Default")
      (node (ref "R17") (pin "6") (pinfunction "6_6") (pintype "passive"))
      (node (ref "U8") (pin "5") (pinfunction "A3_5") (pintype "bidirectional"))
    )
    (net (code "119") (name "Net-(U8-A4)") (class "Default")
      (node (ref "R17") (pin "5") (pinfunction "5_5") (pintype "passive"))
      (node (ref "U8") (pin "6") (pinfunction "A4_6") (pintype "bidirectional"))
    )
    (net (code "120") (name "Net-(U8-A5)") (class "Default")
      (node (ref "R19") (pin "8") (pinfunction "8_8") (pintype "passive"))
      (node (ref "U8") (pin "7") (pinfunction "A5_7") (pintype "bidirectional"))
    )
    (net (code "121") (name "Net-(U8-A6)") (class "Default")
      (node (ref "R19") (pin "7") (pinfunction "7_7") (pintype "passive"))
      (node (ref "U8") (pin "8") (pinfunction "A6_8") (pintype "bidirectional"))
    )
    (net (code "122") (name "Net-(U8-A7)") (class "Default")
      (node (ref "R19") (pin "6") (pinfunction "6_6") (pintype "passive"))
      (node (ref "U8") (pin "9") (pinfunction "A7_9") (pintype "bidirectional"))
    )
    (net (code "123") (name "Net-(U8-A8)") (class "Default")
      (node (ref "R19") (pin "5") (pinfunction "5_5") (pintype "passive"))
      (node (ref "U8") (pin "10") (pinfunction "A8_10") (pintype "bidirectional"))
    )
    (net (code "124") (name "Net-(U8-B1)") (class "Default")
      (node (ref "R18") (pin "1") (pinfunction "1_1") (pintype "passive"))
      (node (ref "U8") (pin "21") (pinfunction "B1_21") (pintype "bidirectional"))
    )
    (net (code "125") (name "Net-(U8-B2)") (class "Default")
      (node (ref "R18") (pin "2") (pinfunction "2_2") (pintype "passive"))
      (node (ref "U8") (pin "20") (pinfunction "B2_20") (pintype "bidirectional"))
    )
    (net (code "126") (name "Net-(U8-B3)") (class "Default")
      (node (ref "R18") (pin "3") (pinfunction "3_3") (pintype "passive"))
      (node (ref "U8") (pin "19") (pinfunction "B3_19") (pintype "bidirectional"))
    )
    (net (code "127") (name "Net-(U8-B4)") (class "Default")
      (node (ref "R18") (pin "4") (pinfunction "4_4") (pintype "passive"))
      (node (ref "U8") (pin "18") (pinfunction "B4_18") (pintype "bidirectional"))
    )
    (net (code "128") (name "Net-(U8-DIR)") (class "Default")
      (node (ref "R31") (pin "1") (pinfunction "1_1") (pintype "passive"))
      (node (ref "U8") (pin "2") (pinfunction "DIR_2") (pintype "input"))
    )
    (net (code "129") (name "Net-(U8-~{OE})") (class "Default")
      (node (ref "R30") (pin "1") (pinfunction "1_1") (pintype "passive"))
      (node (ref "U8") (pin "22") (pinfunction "~{OE}_22") (pintype "input"))
    )
    (net (code "130") (name "Net-(U9-CLKO{slash}SOF)") (class "Default")
      (node (ref "R21") (pin "2") (pinfunction "2_2") (pintype "passive"))
      (node (ref "U9") (pin "3") (pinfunction "CLKO/SOF_3") (pintype "output"))
    )
    (net (code "131") (name "Net-(U9-OSC2)") (class "Default")
      (node (ref "R20") (pin "2") (pinfunction "2_2") (pintype "passive"))
      (node (ref "U9") (pin "5") (pinfunction "OSC2_5") (pintype "output"))
    )
    (net (code "132") (name "unconnected-(P1-Pad8)") (class "Default")
      (node (ref "P1") (pin "8") (pinfunction "8_8") (pintype "passive+no_connect"))
    )
    (net (code "133") (name "unconnected-(R4-Pad5)") (class "Default")
      (node (ref "R4") (pin "5") (pinfunction "5_5") (pintype "passive+no_connect"))
    )
    (net (code "134") (name "unconnected-(R4-Pad6)") (class "Default")
      (node (ref "R4") (pin "6") (pinfunction "6_6") (pintype "passive+no_connect"))
    )
    (net (code "135") (name "unconnected-(R7-Pad5)") (class "Default")
      (node (ref "R7") (pin "5") (pinfunction "5_5") (pintype "passive+no_connect"))
    )
    (net (code "136") (name "unconnected-(R7-Pad6)") (class "Default")
      (node (ref "R7") (pin "6") (pinfunction "6_6") (pintype "passive+no_connect"))
    )
    (net (code "137") (name "unconnected-(R7-Pad7)") (class "Default")
      (node (ref "R7") (pin "7") (pinfunction "7_7") (pintype "passive+no_connect"))
    )
    (net (code "138") (name "unconnected-(R7-Pad8)") (class "Default")
      (node (ref "R7") (pin "8") (pinfunction "8_8") (pintype "passive+no_connect"))
    )
    (net (code "139") (name "unconnected-(R17-Pad2)") (class "Default")
      (node (ref "R17") (pin "2") (pinfunction "2_2") (pintype "passive+no_connect"))
    )
    (net (code "140") (name "unconnected-(R17-Pad3)") (class "Default")
      (node (ref "R17") (pin "3") (pinfunction "3_3") (pintype "passive+no_connect"))
    )
    (net (code "141") (name "unconnected-(R17-Pad4)") (class "Default")
      (node (ref "R17") (pin "4") (pinfunction "4_4") (pintype "passive+no_connect"))
    )
    (net (code "142") (name "unconnected-(U3-CLKOUT-Pad7)") (class "Default")
      (node (ref "U3") (pin "7") (pinfunction "CLKOUT_7") (pintype "output+no_connect"))
    )
    (net (code "143") (name "unconnected-(U3-TX1-Pad14)") (class "Default")
      (node (ref "U3") (pin "14") (pinfunction "TX1_14") (pintype "output+no_connect"))
    )
    (net (code "144") (name "unconnected-(U3-XTAL2-Pad10)") (class "Default")
      (node (ref "U3") (pin "10") (pinfunction "XTAL2_10") (pintype "passive+no_connect"))
    )
  )
)
